# 3DPrinter-PowerDistribution.net
KiCad netlist of a schematic drawn in EAGLE
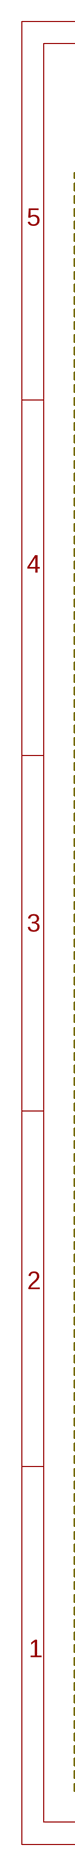
[diagram p0: schematic, sheet 1, part 1 of 2]
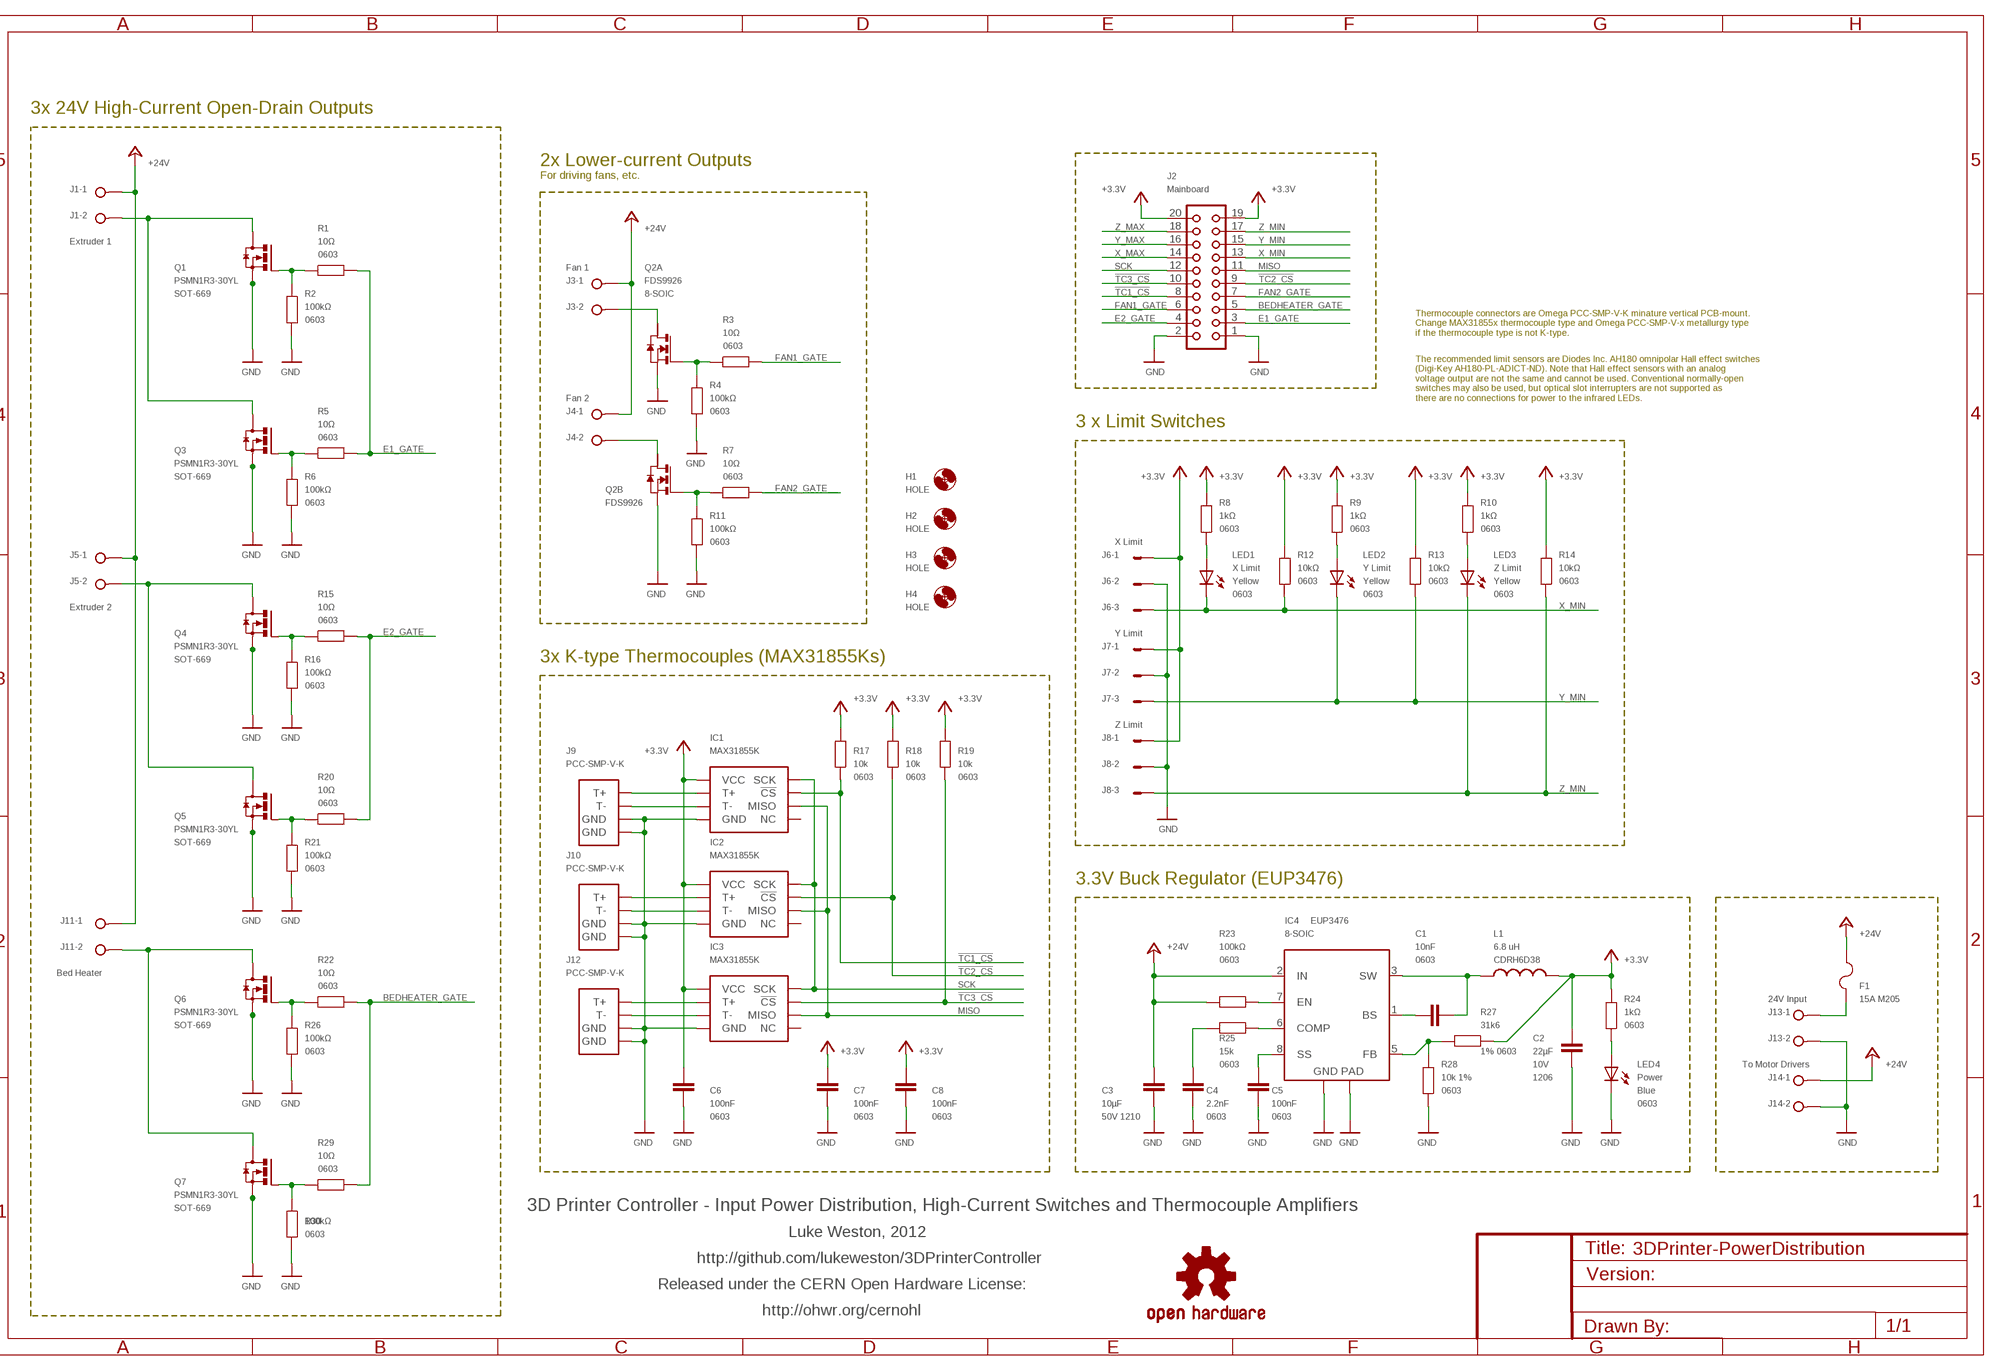
[diagram p1: schematic, sheet 1, part 2 of 2]

(export (version "E")
  (design (tool "Eeschema 10.0.6"))
  (components
    (comp (ref "C1")
      (value "10nF")
      (footprint "eagle-import:0603")
      (fields (field (name "PACKAGE") "0603"))
      (libsource (lib "eagle-import") (part "CAP0603"))
    )
    (comp (ref "C2")
      (value "22µF")
      (footprint "eagle-import:C1206K")
      (fields (field (name "PACKAGE") "1206") (field (name "VOLTAGE") "10V"))
      (libsource (lib "eagle-import") (part "C-EUC1206K"))
    )
    (comp (ref "C3")
      (value "10µF")
      (footprint "eagle-import:C1210K")
      (fields (field (name "VOLTAGE") "50V 1210"))
      (libsource (lib "eagle-import") (part "C-EUC1210K"))
    )
    (comp (ref "C4")
      (value "2.2nF")
      (footprint "eagle-import:0603")
      (fields (field (name "PACKAGE") "0603"))
      (libsource (lib "eagle-import") (part "CAP0603"))
    )
    (comp (ref "C5")
      (value "100nF")
      (footprint "eagle-import:0603")
      (fields (field (name "PACKAGE") "0603"))
      (libsource (lib "eagle-import") (part "CAP0603"))
    )
    (comp (ref "C6")
      (value "100nF")
      (footprint "eagle-import:0603")
      (fields (field (name "PACKAGE") "0603"))
      (libsource (lib "eagle-import") (part "CAP0603"))
    )
    (comp (ref "C7")
      (value "100nF")
      (footprint "eagle-import:0603")
      (fields (field (name "PACKAGE") "0603"))
      (libsource (lib "eagle-import") (part "CAP0603"))
    )
    (comp (ref "C8")
      (value "100nF")
      (footprint "eagle-import:0603")
      (fields (field (name "PACKAGE") "0603"))
      (libsource (lib "eagle-import") (part "CAP0603"))
    )
    (comp (ref "F1")
      (value "15A M205")
      (footprint "eagle-import:SHK20L")
      (libsource (lib "eagle-import") (part "FUSESHK20L"))
    )
    (comp (ref "H1")
      (value "HOLE")
      (footprint "eagle-import:3,2")
      (libsource (lib "eagle-import") (part "MOUNT-HOLE3.2"))
    )
    (comp (ref "H2")
      (value "HOLE")
      (footprint "eagle-import:3,2")
      (libsource (lib "eagle-import") (part "MOUNT-HOLE3.2"))
    )
    (comp (ref "H3")
      (value "HOLE")
      (footprint "eagle-import:3,2")
      (libsource (lib "eagle-import") (part "MOUNT-HOLE3.2"))
    )
    (comp (ref "H4")
      (value "HOLE")
      (footprint "eagle-import:3,2")
      (libsource (lib "eagle-import") (part "MOUNT-HOLE3.2"))
    )
    (comp (ref "IC1")
      (value "MAX31855K")
      (footprint "eagle-import:MCLENG_SOIC-8")
      (libsource (lib "eagle-import") (part "MCLENG_MAX6675MAX31855"))
    )
    (comp (ref "IC2")
      (value "MAX31855K")
      (footprint "eagle-import:MCLENG_SOIC-8")
      (libsource (lib "eagle-import") (part "MCLENG_MAX6675MAX31855"))
    )
    (comp (ref "IC3")
      (value "MAX31855K")
      (footprint "eagle-import:MCLENG_SOIC-8")
      (libsource (lib "eagle-import") (part "MCLENG_MAX6675MAX31855"))
    )
    (comp (ref "IC4")
      (value "EUP3476")
      (footprint "eagle-import:SO08T")
      (fields (field (name "PACKAGE") "8-SOIC"))
      (libsource (lib "eagle-import") (part "EUP3476"))
    )
    (comp (ref "J1")
      (value "Extruder 1")
      (footprint "eagle-import:W237-132")
      (libsource (lib "eagle-import") (part "W237-02P"))
    )
    (comp (ref "J2")
      (value "Mainboard")
      (footprint "eagle-import:CON20L")
      (fields (field (name "OC_FARNELL") "unknown") (field (name "OC_NEWARK") "unknown"))
      (libsource (lib "eagle-import") (part "CON20L"))
    )
    (comp (ref "J3")
      (value "Fan 1")
      (footprint "eagle-import:W237-132")
      (fields (field (name "OC_FARNELL") "unknown") (field (name "OC_NEWARK") "unknown"))
      (libsource (lib "eagle-import") (part "W237-02P"))
    )
    (comp (ref "J4")
      (value "Fan 2")
      (footprint "eagle-import:W237-132")
      (fields (field (name "OC_FARNELL") "unknown") (field (name "OC_NEWARK") "unknown"))
      (libsource (lib "eagle-import") (part "W237-02P"))
    )
    (comp (ref "J5")
      (value "Extruder 2")
      (footprint "eagle-import:W237-132")
      (libsource (lib "eagle-import") (part "W237-02P"))
    )
    (comp (ref "J6")
      (value "X Limit")
      (footprint "eagle-import:7395-03")
      (libsource (lib "eagle-import") (part "22-?-0305-7038"))
    )
    (comp (ref "J7")
      (value "Y Limit")
      (footprint "eagle-import:7395-03")
      (libsource (lib "eagle-import") (part "22-?-0305-7038"))
    )
    (comp (ref "J8")
      (value "Z Limit")
      (footprint "eagle-import:7395-03")
      (libsource (lib "eagle-import") (part "22-?-0305-7038"))
    )
    (comp (ref "J9")
      (value "PCC-SMP-V-K")
      (footprint "eagle-import:MCLAUGHLINENG_TC_JACK")
      (libsource (lib "eagle-import") (part "MCLAUGHLINENG_TC_JACK"))
    )
    (comp (ref "J10")
      (value "PCC-SMP-V-K")
      (footprint "eagle-import:MCLAUGHLINENG_TC_JACK")
      (libsource (lib "eagle-import") (part "MCLAUGHLINENG_TC_JACK"))
    )
    (comp (ref "J11")
      (value "Bed Heater")
      (footprint "eagle-import:W237-132")
      (libsource (lib "eagle-import") (part "W237-02P"))
    )
    (comp (ref "J12")
      (value "PCC-SMP-V-K")
      (footprint "eagle-import:MCLAUGHLINENG_TC_JACK")
      (libsource (lib "eagle-import") (part "MCLAUGHLINENG_TC_JACK"))
    )
    (comp (ref "J13")
      (value "24V Input")
      (footprint "eagle-import:W237-132")
      (libsource (lib "eagle-import") (part "W237-02P"))
    )
    (comp (ref "J14")
      (value "To Motor Drivers")
      (footprint "eagle-import:W237-132")
      (libsource (lib "eagle-import") (part "W237-02P"))
    )
    (comp (ref "L1")
      (value "6.8 uH")
      (footprint "eagle-import:CDRH")
      (fields (field (name "PACKAGE") "CDRH6D38"))
      (libsource (lib "eagle-import") (part "INDUCTOR"))
    )
    (comp (ref "LED1")
      (value "X Limit")
      (footprint "eagle-import:LED-0603")
      (fields (field (name "COLOUR") "Yellow") (field (name "PACKAGE") "0603"))
      (libsource (lib "eagle-import") (part "LED0603"))
    )
    (comp (ref "LED2")
      (value "Y Limit")
      (footprint "eagle-import:LED-0603")
      (fields (field (name "COLOUR") "Yellow") (field (name "PACKAGE") "0603"))
      (libsource (lib "eagle-import") (part "LED0603"))
    )
    (comp (ref "LED3")
      (value "Z Limit")
      (footprint "eagle-import:LED-0603")
      (fields (field (name "COLOUR") "Yellow") (field (name "PACKAGE") "0603"))
      (libsource (lib "eagle-import") (part "LED0603"))
    )
    (comp (ref "LED4")
      (value "Power")
      (footprint "eagle-import:LED-0603")
      (fields (field (name "COLOUR") "Blue") (field (name "PACKAGE") "0603"))
      (libsource (lib "eagle-import") (part "LED0603"))
    )
    (comp (ref "Q1")
      (value "PSMN1R3-30YL")
      (footprint "eagle-import:SOT669")
      (fields (field (name "PACKAGE") "SOT-669"))
      (libsource (lib "eagle-import") (part "PH7030L"))
    )
    (comp (ref "Q2")
      (value "FDS9926")
      (footprint "eagle-import:SM8")
      (fields
        (field (name "OC_FARNELL") "unknown")
        (field (name "OC_NEWARK") "unknown")
        (field (name "PACKAGE") "8-SOIC")
      )
      (libsource (lib "eagle-import") (part "NMOS2SM8"))
    )
    (comp (ref "Q3")
      (value "PSMN1R3-30YL")
      (footprint "eagle-import:SOT669")
      (fields (field (name "PACKAGE") "SOT-669"))
      (libsource (lib "eagle-import") (part "PH7030L"))
    )
    (comp (ref "Q4")
      (value "PSMN1R3-30YL")
      (footprint "eagle-import:SOT669")
      (fields (field (name "PACKAGE") "SOT-669"))
      (libsource (lib "eagle-import") (part "PH7030L"))
    )
    (comp (ref "Q5")
      (value "PSMN1R3-30YL")
      (footprint "eagle-import:SOT669")
      (fields (field (name "PACKAGE") "SOT-669"))
      (libsource (lib "eagle-import") (part "PH7030L"))
    )
    (comp (ref "Q6")
      (value "PSMN1R3-30YL")
      (footprint "eagle-import:SOT669")
      (fields (field (name "PACKAGE") "SOT-669"))
      (libsource (lib "eagle-import") (part "PH7030L"))
    )
    (comp (ref "Q7")
      (value "PSMN1R3-30YL")
      (footprint "eagle-import:SOT669")
      (fields (field (name "PACKAGE") "SOT-669"))
      (libsource (lib "eagle-import") (part "PH7030L"))
    )
    (comp (ref "R1")
      (value "10Ω")
      (footprint "eagle-import:0603")
      (fields (field (name "PACKAGE") "0603"))
      (libsource (lib "eagle-import") (part "RESISTOR0603"))
    )
    (comp (ref "R2")
      (value "100kΩ")
      (footprint "eagle-import:0603")
      (fields (field (name "PACKAGE") "0603"))
      (libsource (lib "eagle-import") (part "RESISTOR0603"))
    )
    (comp (ref "R3")
      (value "10Ω")
      (footprint "eagle-import:0603")
      (fields (field (name "PACKAGE") "0603"))
      (libsource (lib "eagle-import") (part "RESISTOR0603"))
    )
    (comp (ref "R4")
      (value "100kΩ")
      (footprint "eagle-import:0603")
      (fields (field (name "PACKAGE") "0603"))
      (libsource (lib "eagle-import") (part "RESISTOR0603"))
    )
    (comp (ref "R5")
      (value "10Ω")
      (footprint "eagle-import:0603")
      (fields (field (name "PACKAGE") "0603"))
      (libsource (lib "eagle-import") (part "RESISTOR0603"))
    )
    (comp (ref "R6")
      (value "100kΩ")
      (footprint "eagle-import:0603")
      (fields (field (name "PACKAGE") "0603"))
      (libsource (lib "eagle-import") (part "RESISTOR0603"))
    )
    (comp (ref "R7")
      (value "10Ω")
      (footprint "eagle-import:0603")
      (fields (field (name "PACKAGE") "0603"))
      (libsource (lib "eagle-import") (part "RESISTOR0603"))
    )
    (comp (ref "R8")
      (value "1kΩ")
      (footprint "eagle-import:0603")
      (fields (field (name "PACKAGE") "0603"))
      (libsource (lib "eagle-import") (part "RESISTOR0603"))
    )
    (comp (ref "R9")
      (value "1kΩ")
      (footprint "eagle-import:0603")
      (fields (field (name "PACKAGE") "0603"))
      (libsource (lib "eagle-import") (part "RESISTOR0603"))
    )
    (comp (ref "R10")
      (value "1kΩ")
      (footprint "eagle-import:0603")
      (fields (field (name "PACKAGE") "0603"))
      (libsource (lib "eagle-import") (part "RESISTOR0603"))
    )
    (comp (ref "R11")
      (value "100kΩ")
      (footprint "eagle-import:0603")
      (fields (field (name "PACKAGE") "0603"))
      (libsource (lib "eagle-import") (part "RESISTOR0603"))
    )
    (comp (ref "R12")
      (value "10kΩ")
      (footprint "eagle-import:0603")
      (fields (field (name "PACKAGE") "0603"))
      (libsource (lib "eagle-import") (part "RESISTOR0603"))
    )
    (comp (ref "R13")
      (value "10kΩ")
      (footprint "eagle-import:0603")
      (fields (field (name "PACKAGE") "0603"))
      (libsource (lib "eagle-import") (part "RESISTOR0603"))
    )
    (comp (ref "R14")
      (value "10kΩ")
      (footprint "eagle-import:0603")
      (fields (field (name "PACKAGE") "0603"))
      (libsource (lib "eagle-import") (part "RESISTOR0603"))
    )
    (comp (ref "R15")
      (value "10Ω")
      (footprint "eagle-import:0603")
      (fields (field (name "PACKAGE") "0603"))
      (libsource (lib "eagle-import") (part "RESISTOR0603"))
    )
    (comp (ref "R16")
      (value "100kΩ")
      (footprint "eagle-import:0603")
      (fields (field (name "PACKAGE") "0603"))
      (libsource (lib "eagle-import") (part "RESISTOR0603"))
    )
    (comp (ref "R17")
      (value "10k")
      (footprint "eagle-import:0603")
      (fields (field (name "PACKAGE") "0603"))
      (libsource (lib "eagle-import") (part "RESISTOR0603"))
    )
    (comp (ref "R18")
      (value "10k")
      (footprint "eagle-import:0603")
      (fields (field (name "PACKAGE") "0603"))
      (libsource (lib "eagle-import") (part "RESISTOR0603"))
    )
    (comp (ref "R19")
      (value "10k")
      (footprint "eagle-import:0603")
      (fields (field (name "PACKAGE") "0603"))
      (libsource (lib "eagle-import") (part "RESISTOR0603"))
    )
    (comp (ref "R20")
      (value "10Ω")
      (footprint "eagle-import:0603")
      (fields (field (name "PACKAGE") "0603"))
      (libsource (lib "eagle-import") (part "RESISTOR0603"))
    )
    (comp (ref "R21")
      (value "100kΩ")
      (footprint "eagle-import:0603")
      (fields (field (name "PACKAGE") "0603"))
      (libsource (lib "eagle-import") (part "RESISTOR0603"))
    )
    (comp (ref "R22")
      (value "10Ω")
      (footprint "eagle-import:0603")
      (fields (field (name "PACKAGE") "0603"))
      (libsource (lib "eagle-import") (part "RESISTOR0603"))
    )
    (comp (ref "R23")
      (value "100kΩ")
      (footprint "eagle-import:0603")
      (fields (field (name "PACKAGE") "0603"))
      (libsource (lib "eagle-import") (part "RESISTOR0603"))
    )
    (comp (ref "R24")
      (value "1kΩ")
      (footprint "eagle-import:0603")
      (fields (field (name "PACKAGE") "0603"))
      (libsource (lib "eagle-import") (part "RESISTOR0603"))
    )
    (comp (ref "R25")
      (value "15k")
      (footprint "eagle-import:0603")
      (fields (field (name "PACKAGE") "0603"))
      (libsource (lib "eagle-import") (part "RESISTOR0603"))
    )
    (comp (ref "R26")
      (value "100kΩ")
      (footprint "eagle-import:0603")
      (fields (field (name "PACKAGE") "0603"))
      (libsource (lib "eagle-import") (part "RESISTOR0603"))
    )
    (comp (ref "R27")
      (value "31k6")
      (footprint "eagle-import:0603")
      (fields (field (name "PACKAGE") "1% 0603"))
      (libsource (lib "eagle-import") (part "RESISTOR0603"))
    )
    (comp (ref "R28")
      (value "10k 1%")
      (footprint "eagle-import:0603")
      (fields (field (name "PACKAGE") "0603"))
      (libsource (lib "eagle-import") (part "RESISTOR0603"))
    )
    (comp (ref "R29")
      (value "10Ω")
      (footprint "eagle-import:0603")
      (fields (field (name "PACKAGE") "0603"))
      (libsource (lib "eagle-import") (part "RESISTOR0603"))
    )
    (comp (ref "R30")
      (value "100kΩ")
      (footprint "eagle-import:0603")
      (fields (field (name "PACKAGE") "0603"))
      (libsource (lib "eagle-import") (part "RESISTOR0603"))
    )
    (comp (ref "SY")
      (value "OSHW-LOGOS")
      (footprint "eagle-import:OSHW-LOGO-S")
      (libsource (lib "eagle-import") (part "OSHW-LOGOS"))
    )
  )
  (nets
    (net (code "1") (name "+3.3V") (class "Default")
      (node (ref "C2") (pin "1") (pinfunction "1_1") (pintype "passive"))
      (node (ref "C6") (pin "1") (pinfunction "1_1") (pintype "passive"))
      (node (ref "C7") (pin "1") (pinfunction "1_1") (pintype "passive"))
      (node (ref "C8") (pin "1") (pinfunction "1_1") (pintype "passive"))
      (node (ref "IC1") (pin "VCC") (pinfunction "VCC_VCC") (pintype "bidirectional"))
      (node (ref "IC2") (pin "VCC") (pinfunction "VCC_VCC") (pintype "bidirectional"))
      (node (ref "IC3") (pin "VCC") (pinfunction "VCC_VCC") (pintype "bidirectional"))
      (node (ref "J2") (pin "19") (pinfunction "19_19") (pintype "passive"))
      (node (ref "J2") (pin "20") (pinfunction "20_20") (pintype "passive"))
      (node (ref "J6") (pin "1") (pinfunction "S_1") (pintype "passive"))
      (node (ref "J7") (pin "1") (pinfunction "S_1") (pintype "passive"))
      (node (ref "J8") (pin "1") (pinfunction "S_1") (pintype "passive"))
      (node (ref "L1") (pin "2") (pinfunction "2_2") (pintype "bidirectional"))
      (node (ref "R10") (pin "1") (pinfunction "1_1") (pintype "passive"))
      (node (ref "R12") (pin "1") (pinfunction "1_1") (pintype "passive"))
      (node (ref "R13") (pin "1") (pinfunction "1_1") (pintype "passive"))
      (node (ref "R14") (pin "1") (pinfunction "1_1") (pintype "passive"))
      (node (ref "R17") (pin "1") (pinfunction "1_1") (pintype "passive"))
      (node (ref "R18") (pin "1") (pinfunction "1_1") (pintype "passive"))
      (node (ref "R19") (pin "1") (pinfunction "1_1") (pintype "passive"))
      (node (ref "R24") (pin "1") (pinfunction "1_1") (pintype "passive"))
      (node (ref "R27") (pin "1") (pinfunction "1_1") (pintype "passive"))
      (node (ref "R8") (pin "1") (pinfunction "1_1") (pintype "passive"))
      (node (ref "R9") (pin "1") (pinfunction "1_1") (pintype "passive"))
    )
    (net (code "2") (name "+24V") (class "Default")
      (node (ref "C3") (pin "1") (pinfunction "1_1") (pintype "passive"))
      (node (ref "F1") (pin "2A") (pinfunction "2_2A") (pintype "passive"))
      (node (ref "IC4") (pin "2") (pinfunction "IN_2") (pintype "power_in"))
      (node (ref "J1") (pin "1") (pinfunction "KL_1") (pintype "passive"))
      (node (ref "J11") (pin "1") (pinfunction "KL_1") (pintype "passive"))
      (node (ref "J14") (pin "1") (pinfunction "KL_1") (pintype "passive"))
      (node (ref "J3") (pin "1") (pinfunction "KL_1") (pintype "passive"))
      (node (ref "J4") (pin "1") (pinfunction "KL_1") (pintype "passive"))
      (node (ref "J5") (pin "1") (pinfunction "KL_1") (pintype "passive"))
      (node (ref "R23") (pin "2") (pinfunction "2_2") (pintype "passive"))
    )
    (net (code "3") (name "/BEDHEATER_GATE") (class "Default")
      (node (ref "J2") (pin "5") (pinfunction "5_5") (pintype "passive"))
      (node (ref "R22") (pin "1") (pinfunction "1_1") (pintype "passive"))
      (node (ref "R29") (pin "1") (pinfunction "1_1") (pintype "passive"))
    )
    (net (code "4") (name "/E1_GATE") (class "Default")
      (node (ref "J2") (pin "3") (pinfunction "3_3") (pintype "passive"))
      (node (ref "R1") (pin "1") (pinfunction "1_1") (pintype "passive"))
      (node (ref "R5") (pin "1") (pinfunction "1_1") (pintype "passive"))
    )
    (net (code "5") (name "/E2_GATE") (class "Default")
      (node (ref "J2") (pin "4") (pinfunction "4_4") (pintype "passive"))
      (node (ref "R15") (pin "1") (pinfunction "1_1") (pintype "passive"))
      (node (ref "R20") (pin "1") (pinfunction "1_1") (pintype "passive"))
    )
    (net (code "6") (name "/FAN1_GATE") (class "Default")
      (node (ref "J2") (pin "6") (pinfunction "6_6") (pintype "passive"))
      (node (ref "R3") (pin "1") (pinfunction "1_1") (pintype "passive"))
    )
    (net (code "7") (name "/FAN2_GATE") (class "Default")
      (node (ref "J2") (pin "7") (pinfunction "7_7") (pintype "passive"))
      (node (ref "R7") (pin "1") (pinfunction "1_1") (pintype "passive"))
    )
    (net (code "8") (name "/MISO") (class "Default")
      (node (ref "IC1") (pin "SO") (pinfunction "MISO_SO") (pintype "bidirectional"))
      (node (ref "IC2") (pin "SO") (pinfunction "MISO_SO") (pintype "bidirectional"))
      (node (ref "IC3") (pin "SO") (pinfunction "MISO_SO") (pintype "bidirectional"))
      (node (ref "J2") (pin "11") (pinfunction "11_11") (pintype "passive"))
    )
    (net (code "9") (name "/SCK") (class "Default")
      (node (ref "IC1") (pin "SCK") (pinfunction "SCK_SCK") (pintype "bidirectional"))
      (node (ref "IC2") (pin "SCK") (pinfunction "SCK_SCK") (pintype "bidirectional"))
      (node (ref "IC3") (pin "SCK") (pinfunction "SCK_SCK") (pintype "bidirectional"))
      (node (ref "J2") (pin "12") (pinfunction "12_12") (pintype "passive"))
    )
    (net (code "10") (name "/X_MAX") (class "Default")
      (node (ref "J2") (pin "14") (pinfunction "14_14") (pintype "passive"))
    )
    (net (code "11") (name "/X_MIN") (class "Default")
      (node (ref "J2") (pin "13") (pinfunction "13_13") (pintype "passive"))
      (node (ref "J6") (pin "3") (pinfunction "S_3") (pintype "passive"))
      (node (ref "LED1") (pin "C") (pinfunction "C_C") (pintype "passive"))
      (node (ref "R12") (pin "2") (pinfunction "2_2") (pintype "passive"))
    )
    (net (code "12") (name "/Y_MAX") (class "Default")
      (node (ref "J2") (pin "16") (pinfunction "16_16") (pintype "passive"))
    )
    (net (code "13") (name "/Y_MIN") (class "Default")
      (node (ref "J2") (pin "15") (pinfunction "15_15") (pintype "passive"))
      (node (ref "J7") (pin "3") (pinfunction "S_3") (pintype "passive"))
      (node (ref "LED2") (pin "C") (pinfunction "C_C") (pintype "passive"))
      (node (ref "R13") (pin "2") (pinfunction "2_2") (pintype "passive"))
    )
    (net (code "14") (name "/Z_MAX") (class "Default")
      (node (ref "J2") (pin "18") (pinfunction "18_18") (pintype "passive"))
    )
    (net (code "15") (name "/Z_MIN") (class "Default")
      (node (ref "J2") (pin "17") (pinfunction "17_17") (pintype "passive"))
      (node (ref "J8") (pin "3") (pinfunction "S_3") (pintype "passive"))
      (node (ref "LED3") (pin "C") (pinfunction "C_C") (pintype "passive"))
      (node (ref "R14") (pin "2") (pinfunction "2_2") (pintype "passive"))
    )
    (net (code "16") (name "/~{TC1_CS}") (class "Default")
      (node (ref "IC1") (pin "CS") (pinfunction "~{CS}_CS") (pintype "bidirectional"))
      (node (ref "J2") (pin "8") (pinfunction "8_8") (pintype "passive"))
      (node (ref "R17") (pin "2") (pinfunction "2_2") (pintype "passive"))
    )
    (net (code "17") (name "/~{TC2_CS}") (class "Default")
      (node (ref "IC2") (pin "CS") (pinfunction "~{CS}_CS") (pintype "bidirectional"))
      (node (ref "J2") (pin "9") (pinfunction "9_9") (pintype "passive"))
      (node (ref "R18") (pin "2") (pinfunction "2_2") (pintype "passive"))
    )
    (net (code "18") (name "/~{TC3_CS}") (class "Default")
      (node (ref "IC3") (pin "CS") (pinfunction "~{CS}_CS") (pintype "bidirectional"))
      (node (ref "J2") (pin "10") (pinfunction "10_10") (pintype "passive"))
      (node (ref "R19") (pin "2") (pinfunction "2_2") (pintype "passive"))
    )
    (net (code "19") (name "GND") (class "Default")
      (node (ref "C2") (pin "2") (pinfunction "2_2") (pintype "passive"))
      (node (ref "C3") (pin "2") (pinfunction "2_2") (pintype "passive"))
      (node (ref "C4") (pin "1") (pinfunction "1_1") (pintype "passive"))
      (node (ref "C5") (pin "1") (pinfunction "1_1") (pintype "passive"))
      (node (ref "C6") (pin "2") (pinfunction "2_2") (pintype "passive"))
      (node (ref "C7") (pin "2") (pinfunction "2_2") (pintype "passive"))
      (node (ref "C8") (pin "2") (pinfunction "2_2") (pintype "passive"))
      (node (ref "IC1") (pin "GND") (pinfunction "GND_GND") (pintype "bidirectional"))
      (node (ref "IC2") (pin "GND") (pinfunction "GND_GND") (pintype "bidirectional"))
      (node (ref "IC3") (pin "GND") (pinfunction "GND_GND") (pintype "bidirectional"))
      (node (ref "IC4") (pin "4") (pinfunction "GND_4") (pintype "power_in"))
      (node (ref "IC4") (pin "9") (pinfunction "TGND_9") (pintype "power_in"))
      (node (ref "J10") (pin "P$1") (pinfunction "GND_P$1") (pintype "bidirectional"))
      (node (ref "J10") (pin "P$2") (pinfunction "GND_P$2") (pintype "bidirectional"))
      (node (ref "J12") (pin "P$1") (pinfunction "GND_P$1") (pintype "bidirectional"))
      (node (ref "J12") (pin "P$2") (pinfunction "GND_P$2") (pintype "bidirectional"))
      (node (ref "J13") (pin "2") (pinfunction "KL_2") (pintype "passive"))
      (node (ref "J14") (pin "2") (pinfunction "KL_2") (pintype "passive"))
      (node (ref "J2") (pin "1") (pinfunction "1_1") (pintype "passive"))
      (node (ref "J2") (pin "2") (pinfunction "2_2") (pintype "passive"))
      (node (ref "J6") (pin "2") (pinfunction "S_2") (pintype "passive"))
      (node (ref "J7") (pin "2") (pinfunction "S_2") (pintype "passive"))
      (node (ref "J8") (pin "2") (pinfunction "S_2") (pintype "passive"))
      (node (ref "J9") (pin "P$1") (pinfunction "GND_P$1") (pintype "bidirectional"))
      (node (ref "J9") (pin "P$2") (pinfunction "GND_P$2") (pintype "bidirectional"))
      (node (ref "LED4") (pin "C") (pinfunction "C_C") (pintype "passive"))
      (node (ref "Q1") (pin "1") (pinfunction "S_1") (pintype "passive"))
      (node (ref "Q1") (pin "2") (pinfunction "S_2") (pintype "passive"))
      (node (ref "Q1") (pin "3") (pinfunction "S_3") (pintype "passive"))
      (node (ref "Q2") (pin "1") (pinfunction "S_1") (pintype "passive"))
      (node (ref "Q2") (pin "3") (pinfunction "S_3") (pintype "passive"))
      (node (ref "Q3") (pin "1") (pinfunction "S_1") (pintype "passive"))
      (node (ref "Q3") (pin "2") (pinfunction "S_2") (pintype "passive"))
      (node (ref "Q3") (pin "3") (pinfunction "S_3") (pintype "passive"))
      (node (ref "Q4") (pin "1") (pinfunction "S_1") (pintype "passive"))
      (node (ref "Q4") (pin "2") (pinfunction "S_2") (pintype "passive"))
      (node (ref "Q4") (pin "3") (pinfunction "S_3") (pintype "passive"))
      (node (ref "Q5") (pin "1") (pinfunction "S_1") (pintype "passive"))
      (node (ref "Q5") (pin "2") (pinfunction "S_2") (pintype "passive"))
      (node (ref "Q5") (pin "3") (pinfunction "S_3") (pintype "passive"))
      (node (ref "Q6") (pin "1") (pinfunction "S_1") (pintype "passive"))
      (node (ref "Q6") (pin "2") (pinfunction "S_2") (pintype "passive"))
      (node (ref "Q6") (pin "3") (pinfunction "S_3") (pintype "passive"))
      (node (ref "Q7") (pin "1") (pinfunction "S_1") (pintype "passive"))
      (node (ref "Q7") (pin "2") (pinfunction "S_2") (pintype "passive"))
      (node (ref "Q7") (pin "3") (pinfunction "S_3") (pintype "passive"))
      (node (ref "R11") (pin "2") (pinfunction "2_2") (pintype "passive"))
      (node (ref "R16") (pin "2") (pinfunction "2_2") (pintype "passive"))
      (node (ref "R2") (pin "2") (pinfunction "2_2") (pintype "passive"))
      (node (ref "R21") (pin "2") (pinfunction "2_2") (pintype "passive"))
      (node (ref "R26") (pin "2") (pinfunction "2_2") (pintype "passive"))
      (node (ref "R28") (pin "2") (pinfunction "2_2") (pintype "passive"))
      (node (ref "R30") (pin "2") (pinfunction "2_2") (pintype "passive"))
      (node (ref "R4") (pin "2") (pinfunction "2_2") (pintype "passive"))
      (node (ref "R6") (pin "2") (pinfunction "2_2") (pintype "passive"))
    )
    (net (code "20") (name "Net-(C4-Pad2)") (class "Default")
      (node (ref "C4") (pin "2") (pinfunction "2_2") (pintype "passive"))
      (node (ref "R25") (pin "2") (pinfunction "2_2") (pintype "passive"))
    )
    (net (code "21") (name "Net-(F1-1)") (class "Default")
      (node (ref "F1") (pin "1A") (pinfunction "1_1A") (pintype "passive"))
      (node (ref "J13") (pin "1") (pinfunction "KL_1") (pintype "passive"))
    )
    (net (code "22") (name "Net-(IC1-PadT+)") (class "Default")
      (node (ref "IC1") (pin "T+") (pinfunction "T+_T+") (pintype "bidirectional"))
      (node (ref "J9") (pin "T+") (pinfunction "T+_T+") (pintype "bidirectional"))
    )
    (net (code "23") (name "Net-(IC1-PadT-)") (class "Default")
      (node (ref "IC1") (pin "T-") (pinfunction "T-_T-") (pintype "bidirectional"))
      (node (ref "J9") (pin "T-") (pinfunction "T-_T-") (pintype "bidirectional"))
    )
    (net (code "24") (name "Net-(IC2-PadT+)") (class "Default")
      (node (ref "IC2") (pin "T+") (pinfunction "T+_T+") (pintype "bidirectional"))
      (node (ref "J10") (pin "T+") (pinfunction "T+_T+") (pintype "bidirectional"))
    )
    (net (code "25") (name "Net-(IC2-PadT-)") (class "Default")
      (node (ref "IC2") (pin "T-") (pinfunction "T-_T-") (pintype "bidirectional"))
      (node (ref "J10") (pin "T-") (pinfunction "T-_T-") (pintype "bidirectional"))
    )
    (net (code "26") (name "Net-(IC3-PadT+)") (class "Default")
      (node (ref "IC3") (pin "T+") (pinfunction "T+_T+") (pintype "bidirectional"))
      (node (ref "J12") (pin "T+") (pinfunction "T+_T+") (pintype "bidirectional"))
    )
    (net (code "27") (name "Net-(IC3-PadT-)") (class "Default")
      (node (ref "IC3") (pin "T-") (pinfunction "T-_T-") (pintype "bidirectional"))
      (node (ref "J12") (pin "T-") (pinfunction "T-_T-") (pintype "bidirectional"))
    )
    (net (code "28") (name "Net-(IC4-BS)") (class "Default")
      (node (ref "C1") (pin "2") (pinfunction "2_2") (pintype "passive"))
      (node (ref "IC4") (pin "1") (pinfunction "BS_1") (pintype "bidirectional"))
    )
    (net (code "29") (name "Net-(IC4-COMP)") (class "Default")
      (node (ref "IC4") (pin "6") (pinfunction "COMP_6") (pintype "bidirectional"))
      (node (ref "R25") (pin "1") (pinfunction "1_1") (pintype "passive"))
    )
    (net (code "30") (name "Net-(IC4-EN)") (class "Default")
      (node (ref "IC4") (pin "7") (pinfunction "EN_7") (pintype "input"))
      (node (ref "R23") (pin "1") (pinfunction "1_1") (pintype "passive"))
    )
    (net (code "31") (name "Net-(IC4-FB)") (class "Default")
      (node (ref "IC4") (pin "5") (pinfunction "FB_5") (pintype "bidirectional"))
      (node (ref "R27") (pin "2") (pinfunction "2_2") (pintype "passive"))
      (node (ref "R28") (pin "1") (pinfunction "1_1") (pintype "passive"))
    )
    (net (code "32") (name "Net-(IC4-SS)") (class "Default")
      (node (ref "C5") (pin "2") (pinfunction "2_2") (pintype "passive"))
      (node (ref "IC4") (pin "8") (pinfunction "SS_8") (pintype "bidirectional"))
    )
    (net (code "33") (name "Net-(IC4-SW)") (class "Default")
      (node (ref "C1") (pin "1") (pinfunction "1_1") (pintype "passive"))
      (node (ref "IC4") (pin "3") (pinfunction "SW_3") (pintype "bidirectional"))
      (node (ref "L1") (pin "1") (pinfunction "1_1") (pintype "bidirectional"))
    )
    (net (code "34") (name "Net-(J1B-KL)") (class "Default")
      (node (ref "J1") (pin "2") (pinfunction "KL_2") (pintype "passive"))
      (node (ref "Q1") (pin "MB") (pinfunction "D_MB") (pintype "passive"))
      (node (ref "Q3") (pin "MB") (pinfunction "D_MB") (pintype "passive"))
    )
    (net (code "35") (name "Net-(J3B-KL)") (class "Default")
      (node (ref "J3") (pin "2") (pinfunction "KL_2") (pintype "passive"))
      (node (ref "Q2") (pin "5") (pinfunction "D_5") (pintype "passive"))
    )
    (net (code "36") (name "Net-(J4B-KL)") (class "Default")
      (node (ref "J4") (pin "2") (pinfunction "KL_2") (pintype "passive"))
      (node (ref "Q2") (pin "7") (pinfunction "D_7") (pintype "passive"))
    )
    (net (code "37") (name "Net-(J5B-KL)") (class "Default")
      (node (ref "J5") (pin "2") (pinfunction "KL_2") (pintype "passive"))
      (node (ref "Q4") (pin "MB") (pinfunction "D_MB") (pintype "passive"))
      (node (ref "Q5") (pin "MB") (pinfunction "D_MB") (pintype "passive"))
    )
    (net (code "38") (name "Net-(J11B-KL)") (class "Default")
      (node (ref "J11") (pin "2") (pinfunction "KL_2") (pintype "passive"))
      (node (ref "Q6") (pin "MB") (pinfunction "D_MB") (pintype "passive"))
      (node (ref "Q7") (pin "MB") (pinfunction "D_MB") (pintype "passive"))
    )
    (net (code "39") (name "Net-(LED1-PadA)") (class "Default")
      (node (ref "LED1") (pin "A") (pinfunction "A_A") (pintype "passive"))
      (node (ref "R8") (pin "2") (pinfunction "2_2") (pintype "passive"))
    )
    (net (code "40") (name "Net-(LED2-PadA)") (class "Default")
      (node (ref "LED2") (pin "A") (pinfunction "A_A") (pintype "passive"))
      (node (ref "R9") (pin "2") (pinfunction "2_2") (pintype "passive"))
    )
    (net (code "41") (name "Net-(LED3-PadA)") (class "Default")
      (node (ref "LED3") (pin "A") (pinfunction "A_A") (pintype "passive"))
      (node (ref "R10") (pin "2") (pinfunction "2_2") (pintype "passive"))
    )
    (net (code "42") (name "Net-(LED4-PadA)") (class "Default")
      (node (ref "LED4") (pin "A") (pinfunction "A_A") (pintype "passive"))
      (node (ref "R24") (pin "2") (pinfunction "2_2") (pintype "passive"))
    )
    (net (code "43") (name "Net-(Q1-G)") (class "Default")
      (node (ref "Q1") (pin "4") (pinfunction "G_4") (pintype "passive"))
      (node (ref "R1") (pin "2") (pinfunction "2_2") (pintype "passive"))
      (node (ref "R2") (pin "1") (pinfunction "1_1") (pintype "passive"))
    )
    (net (code "44") (name "Net-(Q2A-G)") (class "Default")
      (node (ref "Q2") (pin "4") (pinfunction "G_4") (pintype "passive"))
      (node (ref "R3") (pin "2") (pinfunction "2_2") (pintype "passive"))
      (node (ref "R4") (pin "1") (pinfunction "1_1") (pintype "passive"))
    )
    (net (code "45") (name "Net-(Q2B-G)") (class "Default")
      (node (ref "Q2") (pin "2") (pinfunction "G_2") (pintype "passive"))
      (node (ref "R11") (pin "1") (pinfunction "1_1") (pintype "passive"))
      (node (ref "R7") (pin "2") (pinfunction "2_2") (pintype "passive"))
    )
    (net (code "46") (name "Net-(Q3-G)") (class "Default")
      (node (ref "Q3") (pin "4") (pinfunction "G_4") (pintype "passive"))
      (node (ref "R5") (pin "2") (pinfunction "2_2") (pintype "passive"))
      (node (ref "R6") (pin "1") (pinfunction "1_1") (pintype "passive"))
    )
    (net (code "47") (name "Net-(Q4-G)") (class "Default")
      (node (ref "Q4") (pin "4") (pinfunction "G_4") (pintype "passive"))
      (node (ref "R15") (pin "2") (pinfunction "2_2") (pintype "passive"))
      (node (ref "R16") (pin "1") (pinfunction "1_1") (pintype "passive"))
    )
    (net (code "48") (name "Net-(Q5-G)") (class "Default")
      (node (ref "Q5") (pin "4") (pinfunction "G_4") (pintype "passive"))
      (node (ref "R20") (pin "2") (pinfunction "2_2") (pintype "passive"))
      (node (ref "R21") (pin "1") (pinfunction "1_1") (pintype "passive"))
    )
    (net (code "49") (name "Net-(Q6-G)") (class "Default")
      (node (ref "Q6") (pin "4") (pinfunction "G_4") (pintype "passive"))
      (node (ref "R22") (pin "2") (pinfunction "2_2") (pintype "passive"))
      (node (ref "R26") (pin "1") (pinfunction "1_1") (pintype "passive"))
    )
    (net (code "50") (name "Net-(Q7-G)") (class "Default")
      (node (ref "Q7") (pin "4") (pinfunction "G_4") (pintype "passive"))
      (node (ref "R29") (pin "2") (pinfunction "2_2") (pintype "passive"))
      (node (ref "R30") (pin "1") (pinfunction "1_1") (pintype "passive"))
    )
    (net (code "51") (name "unconnected-(IC1-PadNC)") (class "Default")
      (node (ref "IC1") (pin "NC") (pinfunction "NC_NC") (pintype "no_connect"))
    )
    (net (code "52") (name "unconnected-(IC2-PadNC)") (class "Default")
      (node (ref "IC2") (pin "NC") (pinfunction "NC_NC") (pintype "no_connect"))
    )
    (net (code "53") (name "unconnected-(IC3-PadNC)") (class "Default")
      (node (ref "IC3") (pin "NC") (pinfunction "NC_NC") (pintype "no_connect"))
    )
    (net (code "54") (name "unconnected-(Q2A-D2-Pad6)") (class "Default")
      (node (ref "Q2") (pin "6") (pinfunction "D2_6") (pintype "passive"))
    )
    (net (code "55") (name "unconnected-(Q2B-D2-Pad8)") (class "Default")
      (node (ref "Q2") (pin "8") (pinfunction "D2_8") (pintype "passive"))
    )
  )
)
